# MidDin.net
KiCad netlist of a schematic drawn in Altium Designer
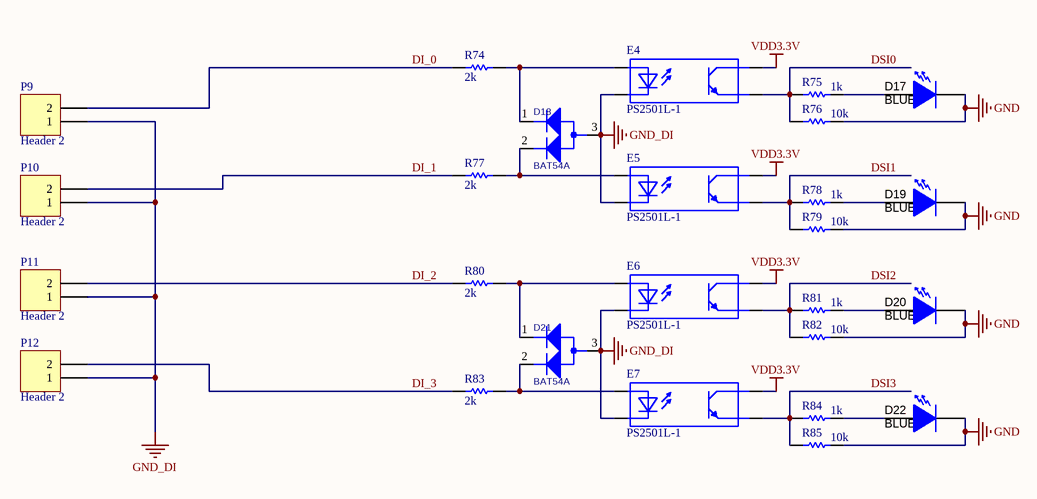
[diagram p0: MidDin.SchDoc]

(export (version "E")
  (design (tool "Eeschema 10.0.6"))
  (components
    (comp (ref "D17")
      (value "BLUE")
      (footprint "D0805")
      (description "LED, GREEN SMD")
      (fields
        (field (name "MANUFACTURER") "Rohm")
        (field (name "PARTNUMBER") "SML-P12YTT86")
        (field (name "PUBLISHER") "Texas Instruments")
      )
      (libsource (lib "REl") (part "SML-P12YTT86"))
    )
    (comp (ref "D18") (value "BAT54A") (footprint "SOT23") (libsource (lib "*") (part "BAT54A/SOT_2")))
    (comp (ref "D19")
      (value "BLUE")
      (footprint "D0805")
      (description "LED, GREEN SMD")
      (fields
        (field (name "MANUFACTURER") "Rohm")
        (field (name "PARTNUMBER") "SML-P12YTT86")
        (field (name "PUBLISHER") "Texas Instruments")
      )
      (libsource (lib "REl") (part "SML-P12YTT86"))
    )
    (comp (ref "D20")
      (value "BLUE")
      (footprint "D0805")
      (description "LED, GREEN SMD")
      (fields
        (field (name "MANUFACTURER") "Rohm")
        (field (name "PARTNUMBER") "SML-P12YTT86")
        (field (name "PUBLISHER") "Texas Instruments")
      )
      (libsource (lib "REl") (part "SML-P12YTT86"))
    )
    (comp (ref "D21") (value "BAT54A") (footprint "SOT23") (libsource (lib "*") (part "BAT54A/SOT_2")))
    (comp (ref "D22")
      (value "BLUE")
      (footprint "D0805")
      (description "LED, GREEN SMD")
      (fields
        (field (name "MANUFACTURER") "Rohm")
        (field (name "PARTNUMBER") "SML-P12YTT86")
        (field (name "PUBLISHER") "Texas Instruments")
      )
      (libsource (lib "REl") (part "SML-P12YTT86"))
    )
    (comp (ref "E4") (value "PS2501L-1") (description "光耦") (libsource (lib "*") (part "OPTO1")))
    (comp (ref "E5") (value "PS2501L-1") (description "光耦") (libsource (lib "*") (part "OPTO1")))
    (comp (ref "E6") (value "PS2501L-1") (description "光耦") (libsource (lib "*") (part "OPTO1")))
    (comp (ref "E7") (value "PS2501L-1") (description "光耦") (libsource (lib "*") (part "OPTO1")))
    (comp (ref "P9")
      (value "Header 2")
      (footprint "3.5-P2")
      (description "Header, 2-Pin")
      (fields (field (name "PUBLISHER") "Altium Limited"))
      (libsource (lib "Miscellaneous Connectors") (part "Header 2"))
    )
    (comp (ref "P10")
      (value "Header 2")
      (footprint "3.5-P2")
      (description "Header, 2-Pin")
      (fields (field (name "PUBLISHER") "Altium Limited"))
      (libsource (lib "Miscellaneous Connectors") (part "Header 2"))
    )
    (comp (ref "P11")
      (value "Header 2")
      (footprint "3.5-P2")
      (description "Header, 2-Pin")
      (fields (field (name "PUBLISHER") "Altium Limited"))
      (libsource (lib "Miscellaneous Connectors") (part "Header 2"))
    )
    (comp (ref "P12")
      (value "Header 2")
      (footprint "3.5-P2")
      (description "Header, 2-Pin")
      (fields (field (name "PUBLISHER") "Altium Limited"))
      (libsource (lib "Miscellaneous Connectors") (part "Header 2"))
    )
    (comp (ref "R74")
      (value "2k")
      (footprint "0805")
      (description "Semiconductor Resistor")
      (fields (field (name "Comment") "Res Semi") (field (name "PUBLISHER") "Altium Limited"))
      (libsource (lib "Miscellaneous Devices") (part "Res Semi"))
    )
    (comp (ref "R75")
      (value "1k")
      (footprint "0805")
      (description "Semiconductor Resistor")
      (fields (field (name "Comment") "Res Semi") (field (name "PUBLISHER") "Altium Limited"))
      (libsource (lib "Miscellaneous Devices") (part "Res Semi"))
    )
    (comp (ref "R76")
      (value "10k")
      (footprint "0805")
      (description "Semiconductor Resistor")
      (fields (field (name "Comment") "Res Semi") (field (name "PUBLISHER") "Altium Limited"))
      (libsource (lib "Miscellaneous Devices") (part "Res Semi"))
    )
    (comp (ref "R77")
      (value "2k")
      (footprint "0805")
      (description "Semiconductor Resistor")
      (fields (field (name "Comment") "Res Semi") (field (name "PUBLISHER") "Altium Limited"))
      (libsource (lib "Miscellaneous Devices") (part "Res Semi"))
    )
    (comp (ref "R78")
      (value "1k")
      (footprint "0805")
      (description "Semiconductor Resistor")
      (fields (field (name "Comment") "Res Semi") (field (name "PUBLISHER") "Altium Limited"))
      (libsource (lib "Miscellaneous Devices") (part "Res Semi"))
    )
    (comp (ref "R79")
      (value "10k")
      (footprint "0805")
      (description "Semiconductor Resistor")
      (fields (field (name "Comment") "Res Semi") (field (name "PUBLISHER") "Altium Limited"))
      (libsource (lib "Miscellaneous Devices") (part "Res Semi"))
    )
    (comp (ref "R80")
      (value "2k")
      (footprint "0805")
      (description "Semiconductor Resistor")
      (fields (field (name "Comment") "Res Semi") (field (name "PUBLISHER") "Altium Limited"))
      (libsource (lib "Miscellaneous Devices") (part "Res Semi"))
    )
    (comp (ref "R81")
      (value "1k")
      (footprint "0805")
      (description "Semiconductor Resistor")
      (fields (field (name "Comment") "Res Semi") (field (name "PUBLISHER") "Altium Limited"))
      (libsource (lib "Miscellaneous Devices") (part "Res Semi"))
    )
    (comp (ref "R82")
      (value "10k")
      (footprint "0805")
      (description "Semiconductor Resistor")
      (fields (field (name "Comment") "Res Semi") (field (name "PUBLISHER") "Altium Limited"))
      (libsource (lib "Miscellaneous Devices") (part "Res Semi"))
    )
    (comp (ref "R83")
      (value "2k")
      (footprint "0805")
      (description "Semiconductor Resistor")
      (fields (field (name "Comment") "Res Semi") (field (name "PUBLISHER") "Altium Limited"))
      (libsource (lib "Miscellaneous Devices") (part "Res Semi"))
    )
    (comp (ref "R84")
      (value "1k")
      (footprint "0805")
      (description "Semiconductor Resistor")
      (fields (field (name "Comment") "Res Semi") (field (name "PUBLISHER") "Altium Limited"))
      (libsource (lib "Miscellaneous Devices") (part "Res Semi"))
    )
    (comp (ref "R85")
      (value "10k")
      (footprint "0805")
      (description "Semiconductor Resistor")
      (fields (field (name "Comment") "Res Semi") (field (name "PUBLISHER") "Altium Limited"))
      (libsource (lib "Miscellaneous Devices") (part "Res Semi"))
    )
  )
  (nets
    (net (code "1") (name "/DI_0") (class "Default")
      (node (ref "P9") (pin "2") (pinfunction "2_2") (pintype "passive"))
      (node (ref "R74") (pin "1") (pinfunction "1_1") (pintype "passive"))
    )
    (net (code "2") (name "/DI_1") (class "Default")
      (node (ref "P10") (pin "2") (pinfunction "2_2") (pintype "passive"))
      (node (ref "R77") (pin "1") (pinfunction "1_1") (pintype "passive"))
    )
    (net (code "3") (name "/DI_2") (class "Default")
      (node (ref "P11") (pin "2") (pinfunction "2_2") (pintype "passive"))
      (node (ref "R80") (pin "1") (pinfunction "1_1") (pintype "passive"))
    )
    (net (code "4") (name "/DI_3") (class "Default")
      (node (ref "P12") (pin "2") (pinfunction "2_2") (pintype "passive"))
      (node (ref "R83") (pin "1") (pinfunction "1_1") (pintype "passive"))
    )
    (net (code "5") (name "/DSI0") (class "Default")
      (node (ref "E4") (pin "3") (pintype "passive"))
      (node (ref "R75") (pin "1") (pinfunction "1_1") (pintype "passive"))
      (node (ref "R76") (pin "1") (pinfunction "1_1") (pintype "passive"))
    )
    (net (code "6") (name "/DSI1") (class "Default")
      (node (ref "E5") (pin "3") (pintype "passive"))
      (node (ref "R78") (pin "1") (pinfunction "1_1") (pintype "passive"))
      (node (ref "R79") (pin "1") (pinfunction "1_1") (pintype "passive"))
    )
    (net (code "7") (name "/DSI2") (class "Default")
      (node (ref "E6") (pin "3") (pintype "passive"))
      (node (ref "R81") (pin "1") (pinfunction "1_1") (pintype "passive"))
      (node (ref "R82") (pin "1") (pinfunction "1_1") (pintype "passive"))
    )
    (net (code "8") (name "/DSI3") (class "Default")
      (node (ref "E7") (pin "3") (pintype "passive"))
      (node (ref "R84") (pin "1") (pinfunction "1_1") (pintype "passive"))
      (node (ref "R85") (pin "1") (pinfunction "1_1") (pintype "passive"))
    )
    (net (code "9") (name "GND") (class "Default")
      (node (ref "D17") (pin "2") (pinfunction "K_2") (pintype "passive"))
      (node (ref "D19") (pin "2") (pinfunction "K_2") (pintype "passive"))
      (node (ref "D20") (pin "2") (pinfunction "K_2") (pintype "passive"))
      (node (ref "D22") (pin "2") (pinfunction "K_2") (pintype "passive"))
      (node (ref "R76") (pin "2") (pinfunction "2_2") (pintype "passive"))
      (node (ref "R79") (pin "2") (pinfunction "2_2") (pintype "passive"))
      (node (ref "R82") (pin "2") (pinfunction "2_2") (pintype "passive"))
      (node (ref "R85") (pin "2") (pinfunction "2_2") (pintype "passive"))
    )
    (net (code "10") (name "GND_DI") (class "Default")
      (node (ref "D18") (pin "3") (pinfunction "3_3") (pintype "passive"))
      (node (ref "D21") (pin "3") (pinfunction "3_3") (pintype "passive"))
      (node (ref "E4") (pin "2") (pintype "passive"))
      (node (ref "E5") (pin "2") (pintype "passive"))
      (node (ref "E6") (pin "2") (pintype "passive"))
      (node (ref "E7") (pin "2") (pintype "passive"))
      (node (ref "P10") (pin "1") (pinfunction "1_1") (pintype "passive"))
      (node (ref "P11") (pin "1") (pinfunction "1_1") (pintype "passive"))
      (node (ref "P12") (pin "1") (pinfunction "1_1") (pintype "passive"))
      (node (ref "P9") (pin "1") (pinfunction "1_1") (pintype "passive"))
    )
    (net (code "11") (name "Net-(D17-A)") (class "Default")
      (node (ref "D17") (pin "1") (pinfunction "A_1") (pintype "passive"))
      (node (ref "R75") (pin "2") (pinfunction "2_2") (pintype "passive"))
    )
    (net (code "12") (name "Net-(D18-Pad1)") (class "Default")
      (node (ref "D18") (pin "1") (pinfunction "1_1") (pintype "passive"))
      (node (ref "E4") (pin "1") (pintype "passive"))
      (node (ref "R74") (pin "2") (pinfunction "2_2") (pintype "passive"))
    )
    (net (code "13") (name "Net-(D18-Pad2)") (class "Default")
      (node (ref "D18") (pin "2") (pinfunction "2_2") (pintype "passive"))
      (node (ref "E5") (pin "1") (pintype "passive"))
      (node (ref "R77") (pin "2") (pinfunction "2_2") (pintype "passive"))
    )
    (net (code "14") (name "Net-(D19-A)") (class "Default")
      (node (ref "D19") (pin "1") (pinfunction "A_1") (pintype "passive"))
      (node (ref "R78") (pin "2") (pinfunction "2_2") (pintype "passive"))
    )
    (net (code "15") (name "Net-(D20-A)") (class "Default")
      (node (ref "D20") (pin "1") (pinfunction "A_1") (pintype "passive"))
      (node (ref "R81") (pin "2") (pinfunction "2_2") (pintype "passive"))
    )
    (net (code "16") (name "Net-(D21-Pad1)") (class "Default")
      (node (ref "D21") (pin "1") (pinfunction "1_1") (pintype "passive"))
      (node (ref "E6") (pin "1") (pintype "passive"))
      (node (ref "R80") (pin "2") (pinfunction "2_2") (pintype "passive"))
    )
    (net (code "17") (name "Net-(D21-Pad2)") (class "Default")
      (node (ref "D21") (pin "2") (pinfunction "2_2") (pintype "passive"))
      (node (ref "E7") (pin "1") (pintype "passive"))
      (node (ref "R83") (pin "2") (pinfunction "2_2") (pintype "passive"))
    )
    (net (code "18") (name "Net-(D22-A)") (class "Default")
      (node (ref "D22") (pin "1") (pinfunction "A_1") (pintype "passive"))
      (node (ref "R84") (pin "2") (pinfunction "2_2") (pintype "passive"))
    )
    (net (code "19") (name "VDD3.3V") (class "Default")
      (node (ref "E4") (pin "4") (pintype "passive"))
      (node (ref "E5") (pin "4") (pintype "passive"))
      (node (ref "E6") (pin "4") (pintype "passive"))
      (node (ref "E7") (pin "4") (pintype "passive"))
    )
  )
)
